# Home_security.net
KiCad netlist of a schematic drawn in Altium Designer
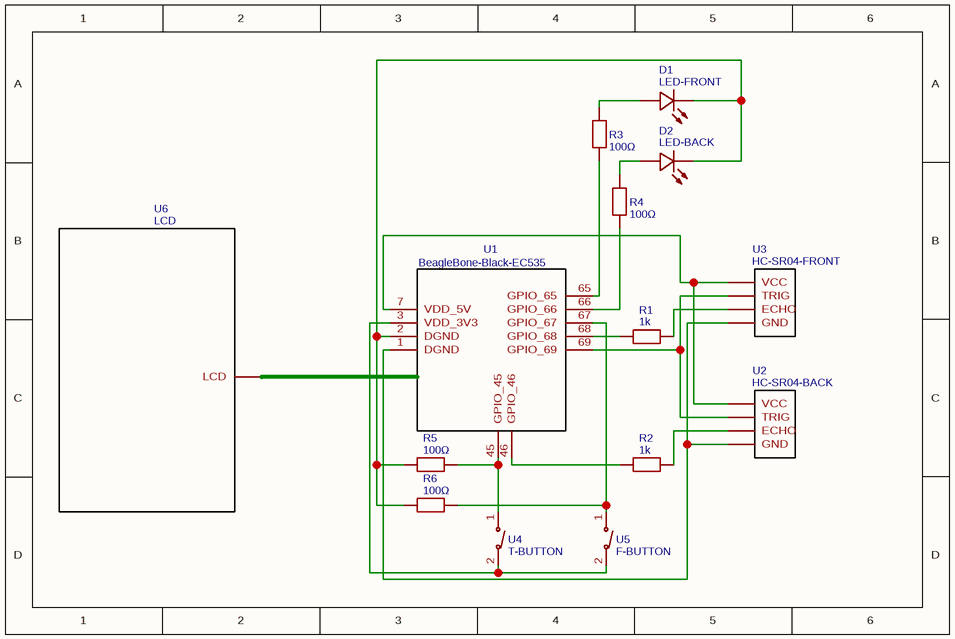
[diagram p0: Home_security.schdoc]

(export (version "E")
  (design (tool "Eeschema 10.0.6"))
  (components
    (comp (ref "D1")
      (value "LED-FRONT")
      (fields
        (field (name "BOM_SUPPLIER PART") "C9900003436")
        (field (name "BOM_MANUFACTURER PART") "LED-DIODE_2")
        (field (name "CONTRIBUTOR") "LCSC")
      )
      (libsource (lib "altium-import") (part "root_2_LED-FRONT_"))
    )
    (comp (ref "D2")
      (value "LED-BACK")
      (fields
        (field (name "BOM_SUPPLIER PART") "C9900003436")
        (field (name "BOM_MANUFACTURER PART") "LED-DIODE_2")
        (field (name "CONTRIBUTOR") "LCSC")
      )
      (libsource (lib "altium-import") (part "root_2_LED-BACK_"))
    )
    (comp (ref "R1")
      (value "1k")
      (fields
        (field (name "BOM_SUPPLIER PART") "C421792")
        (field (name "BOM_MANUFACTURER PART") "201007F6804T4E")
        (field (name "CONTRIBUTOR") "LCSC")
      )
      (libsource (lib "altium-import") (part "root_0_1k_"))
    )
    (comp (ref "R2")
      (value "1k")
      (fields
        (field (name "BOM_SUPPLIER PART") "C421792")
        (field (name "BOM_MANUFACTURER PART") "201007F6804T4E")
        (field (name "CONTRIBUTOR") "LCSC")
      )
      (libsource (lib "altium-import") (part "root_0_1k_"))
    )
    (comp (ref "R3")
      (value "100Ω")
      (fields
        (field (name "BOM_SUPPLIER PART") "C421792")
        (field (name "BOM_MANUFACTURER PART") "201007F6804T4E")
        (field (name "CONTRIBUTOR") "LCSC")
      )
      (libsource (lib "altium-import") (part "root_1_100Ω_"))
    )
    (comp (ref "R4")
      (value "100Ω")
      (fields
        (field (name "BOM_SUPPLIER PART") "C421792")
        (field (name "BOM_MANUFACTURER PART") "201007F6804T4E")
        (field (name "CONTRIBUTOR") "LCSC")
      )
      (libsource (lib "altium-import") (part "root_3_100Ω_"))
    )
    (comp (ref "R5")
      (value "100Ω")
      (fields
        (field (name "BOM_SUPPLIER PART") "C421792")
        (field (name "BOM_MANUFACTURER PART") "201007F6804T4E")
        (field (name "CONTRIBUTOR") "LCSC")
      )
      (libsource (lib "altium-import") (part "root_0_100Ω_"))
    )
    (comp (ref "R6")
      (value "100Ω")
      (fields
        (field (name "BOM_SUPPLIER PART") "C421792")
        (field (name "BOM_MANUFACTURER PART") "201007F6804T4E")
        (field (name "CONTRIBUTOR") "LCSC")
      )
      (libsource (lib "altium-import") (part "root_0_100Ω_"))
    )
    (comp (ref "U1")
      (value "BeagleBone-Black-EC535")
      (fields (field (name "CONTRIBUTOR") "csc0007"))
      (libsource (lib "altium-import") (part "root_0_BeagleBone-Black-EC535_"))
    )
    (comp (ref "U2")
      (value "HC-SR04-BACK")
      (fields (field (name "CONTRIBUTOR") "csc0007"))
      (libsource (lib "altium-import") (part "root_3_HC-SR04-BACK_"))
    )
    (comp (ref "U3")
      (value "HC-SR04-FRONT")
      (fields (field (name "CONTRIBUTOR") "csc0007"))
      (libsource (lib "altium-import") (part "root_3_HC-SR04-FRONT_"))
    )
    (comp (ref "U4")
      (value "T-BUTTON")
      (fields
        (field (name "BOM_SUPPLIER PART") "C9900040040")
        (field (name "BOM_MANUFACTURER PART") "BUTTON")
        (field (name "CONTRIBUTOR") "lcsc")
      )
      (libsource (lib "altium-import") (part "root_3_T-BUTTON_"))
    )
    (comp (ref "U5")
      (value "F-BUTTON")
      (fields
        (field (name "BOM_SUPPLIER PART") "C9900040040")
        (field (name "BOM_MANUFACTURER PART") "BUTTON")
        (field (name "CONTRIBUTOR") "lcsc")
      )
      (libsource (lib "altium-import") (part "root_3_F-BUTTON_"))
    )
    (comp (ref "U6")
      (value "LCD")
      (fields (field (name "CONTRIBUTOR") "csc0007"))
      (libsource (lib "altium-import") (part "root_1_LCD_"))
    )
  )
  (nets
    (net (code "1") (name "Net-(D1-+)") (class "Default")
      (node (ref "D1") (pin "2") (pinfunction "+_2") (pintype "passive"))
      (node (ref "R3") (pin "2") (pinfunction "2_2") (pintype "passive"))
    )
    (net (code "2") (name "Net-(D1--)") (class "Default")
      (node (ref "D1") (pin "1") (pinfunction "-_1") (pintype "passive"))
      (node (ref "D2") (pin "1") (pinfunction "-_1") (pintype "passive"))
      (node (ref "R5") (pin "1") (pinfunction "1_1") (pintype "passive"))
      (node (ref "R6") (pin "1") (pinfunction "1_1") (pintype "passive"))
      (node (ref "U1") (pin "2") (pinfunction "DGND_2") (pintype "passive"))
    )
    (net (code "3") (name "Net-(D2-+)") (class "Default")
      (node (ref "D2") (pin "2") (pinfunction "+_2") (pintype "passive"))
      (node (ref "R4") (pin "1") (pinfunction "1_1") (pintype "passive"))
    )
    (net (code "4") (name "Net-(U1-GPIO_45)") (class "Default")
      (node (ref "R5") (pin "2") (pinfunction "2_2") (pintype "passive"))
      (node (ref "U1") (pin "45") (pinfunction "GPIO_45_45") (pintype "passive"))
      (node (ref "U4") (pin "1") (pinfunction "A_1") (pintype "passive"))
    )
    (net (code "5") (name "Net-(U1-GPIO_46)") (class "Default")
      (node (ref "R2") (pin "1") (pinfunction "1_1") (pintype "passive"))
      (node (ref "U1") (pin "46") (pinfunction "GPIO_46_46") (pintype "passive"))
    )
    (net (code "6") (name "Net-(U1-GPIO_65)") (class "Default")
      (node (ref "R3") (pin "1") (pinfunction "1_1") (pintype "passive"))
      (node (ref "U1") (pin "65") (pinfunction "GPIO_65_65") (pintype "passive"))
    )
    (net (code "7") (name "Net-(U1-GPIO_66)") (class "Default")
      (node (ref "R4") (pin "2") (pinfunction "2_2") (pintype "passive"))
      (node (ref "U1") (pin "66") (pinfunction "GPIO_66_66") (pintype "passive"))
    )
    (net (code "8") (name "Net-(U1-GPIO_67)") (class "Default")
      (node (ref "R6") (pin "2") (pinfunction "2_2") (pintype "passive"))
      (node (ref "U1") (pin "67") (pinfunction "GPIO_67_67") (pintype "passive"))
      (node (ref "U5") (pin "1") (pinfunction "A_1") (pintype "passive"))
    )
    (net (code "9") (name "Net-(U1-GPIO_68)") (class "Default")
      (node (ref "R1") (pin "1") (pinfunction "1_1") (pintype "passive"))
      (node (ref "U1") (pin "68") (pinfunction "GPIO_68_68") (pintype "passive"))
    )
    (net (code "10") (name "Net-(U1-GPIO_69)") (class "Default")
      (node (ref "U1") (pin "69") (pinfunction "GPIO_69_69") (pintype "passive"))
      (node (ref "U2") (pin "6") (pinfunction "TRIG_6") (pintype "passive"))
      (node (ref "U3") (pin "6") (pinfunction "TRIG_6") (pintype "passive"))
    )
    (net (code "11") (name "Net-(U1-VDD_3V3)") (class "Default")
      (node (ref "U1") (pin "3") (pinfunction "VDD_3V3_3") (pintype "passive"))
      (node (ref "U4") (pin "2") (pinfunction "B_2") (pintype "passive"))
      (node (ref "U5") (pin "2") (pinfunction "B_2") (pintype "passive"))
    )
    (net (code "12") (name "Net-(U1-VDD_5V)") (class "Default")
      (node (ref "U1") (pin "7") (pinfunction "VDD_5V_7") (pintype "passive"))
      (node (ref "U2") (pin "1") (pinfunction "VCC_1") (pintype "passive"))
      (node (ref "U3") (pin "1") (pinfunction "VCC_1") (pintype "passive"))
    )
    (net (code "13") (name "Net-(U2-ECHO)") (class "Default")
      (node (ref "R2") (pin "2") (pinfunction "2_2") (pintype "passive"))
      (node (ref "U2") (pin "3") (pinfunction "ECHO_3") (pintype "passive"))
    )
    (net (code "14") (name "Net-(U2-GND)") (class "Default")
      (node (ref "U1") (pin "1") (pinfunction "DGND_1") (pintype "passive"))
      (node (ref "U2") (pin "4") (pinfunction "GND_4") (pintype "passive"))
      (node (ref "U3") (pin "4") (pinfunction "GND_4") (pintype "passive"))
    )
    (net (code "15") (name "Net-(U3-ECHO)") (class "Default")
      (node (ref "R1") (pin "2") (pinfunction "2_2") (pintype "passive"))
      (node (ref "U3") (pin "3") (pinfunction "ECHO_3") (pintype "passive"))
    )
    (net (code "16") (name "unconnected-(U6-LCD-Pad1)") (class "Default")
      (node (ref "U6") (pin "1") (pinfunction "LCD_1") (pintype "passive"))
    )
  )
)
